# DSOXLAN_Schematic.net
KiCad netlist of a schematic drawn in Altium Designer
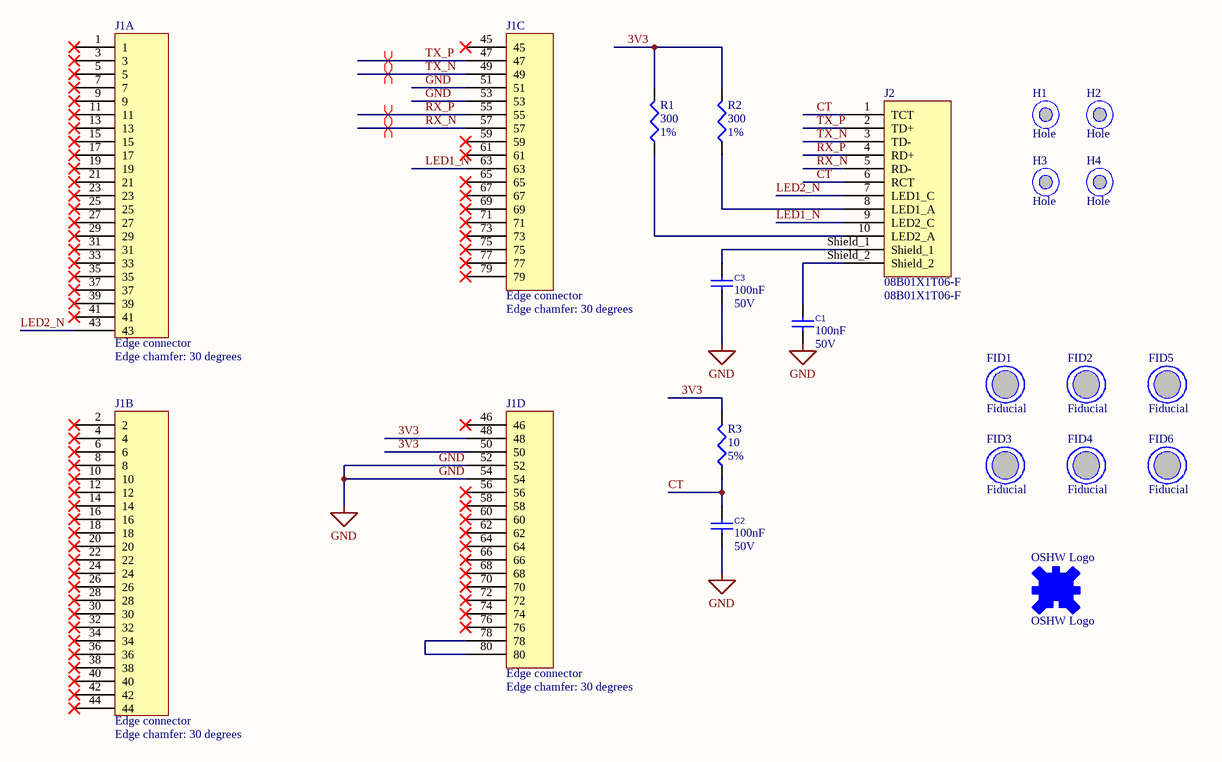
[diagram p0: DSOXLAN Schematic.SchDoc]

(export (version "E")
  (design (tool "Eeschema 10.0.6"))
  (components
    (comp (ref "C1")
      (value "100nF")
      (footprint "CAPC1005N")
      (description "Ceramic capcitor, X7R, 0402, 100nF, 10%, 50V")
      (fields
        (field (name "MANUFACTURER") "Yageo")
        (field (name "TOLERANCE") "10%")
        (field (name "VOLTAGE") "50V")
      )
      (libsource (lib "EnigmaTechComponents") (part "CAPC1005"))
    )
    (comp (ref "C2")
      (value "100nF")
      (footprint "CAPC1005N")
      (description "Ceramic capcitor, X7R, 0402, 100nF, 10%, 50V")
      (fields
        (field (name "MANUFACTURER") "Yageo")
        (field (name "TOLERANCE") "10%")
        (field (name "VOLTAGE") "50V")
      )
      (libsource (lib "EnigmaTechComponents") (part "CAPC1005"))
    )
    (comp (ref "C3")
      (value "100nF")
      (footprint "CAPC1005N")
      (description "Ceramic capcitor, X7R, 0402, 100nF, 10%, 50V")
      (fields
        (field (name "MANUFACTURER") "Yageo")
        (field (name "TOLERANCE") "10%")
        (field (name "VOLTAGE") "50V")
      )
      (libsource (lib "EnigmaTechComponents") (part "CAPC1005"))
    )
    (comp (ref "FID1")
      (value "Fiducial")
      (footprint "Fiducial 1mm")
      (description "Fiducial mark 1mm")
      (libsource (lib "EnigmaTechSCHLib") (part "Fiducial mark"))
    )
    (comp (ref "FID2")
      (value "Fiducial")
      (footprint "Fiducial 1mm")
      (description "Fiducial mark 1mm")
      (libsource (lib "EnigmaTechSCHLib") (part "Fiducial mark"))
    )
    (comp (ref "FID3")
      (value "Fiducial")
      (footprint "Fiducial 1mm")
      (description "Fiducial mark 1mm")
      (libsource (lib "EnigmaTechSCHLib") (part "Fiducial mark"))
    )
    (comp (ref "FID4")
      (value "Fiducial")
      (footprint "Fiducial 1mm")
      (description "Fiducial mark 1mm")
      (libsource (lib "EnigmaTechSCHLib") (part "Fiducial mark"))
    )
    (comp (ref "FID5")
      (value "Fiducial")
      (footprint "Fiducial 1mm")
      (description "Fiducial mark 1mm")
      (libsource (lib "EnigmaTechSCHLib") (part "Fiducial mark"))
    )
    (comp (ref "FID6")
      (value "Fiducial")
      (footprint "Fiducial 1mm")
      (description "Fiducial mark 1mm")
      (libsource (lib "EnigmaTechSCHLib") (part "Fiducial mark"))
    )
    (comp (ref "H1")
      (value "Hole")
      (footprint "Hole 3.2 non plated")
      (description "Non Plated Hole, 3.2mm ID")
      (libsource (lib "EnigmaTechSCHLib") (part "Hole 3.2mm NP"))
    )
    (comp (ref "H2")
      (value "Hole")
      (footprint "Hole 3.2 non plated")
      (description "Non Plated Hole, 3.2mm ID")
      (libsource (lib "EnigmaTechSCHLib") (part "Hole 3.2mm NP"))
    )
    (comp (ref "H3")
      (value "Hole")
      (footprint "Hole 3.2 non plated")
      (description "Non Plated Hole, 3.2mm ID")
      (libsource (lib "EnigmaTechSCHLib") (part "Hole 3.2mm NP"))
    )
    (comp (ref "H4")
      (value "Hole")
      (footprint "Hole 3.2 non plated")
      (description "Non Plated Hole, 3.2mm ID")
      (libsource (lib "EnigmaTechSCHLib") (part "Hole 3.2mm NP"))
    )
    (comp (ref "J1")
      (value "Edge connector")
      (footprint "Edge Connector 0.8mm 80P")
      (description "Edge contact 80pos 0.8p")
      (fields (field (name "EDGE CHAMFER") "30 degrees"))
      (libsource (lib "EnigmaTechConnectors") (part "Edge Connector 0.8mm 80 Pos"))
    )
    (comp (ref "J2")
      (value "08B01X1T06-F")
      (footprint "RJ45 BEL 08B0-1X1T-06-F")
      (description "RJ45 TH With magnetics")
      (fields
        (field (name "MANUFACTURER") "Bel Fuse")
        (field (name "MANUFACTURER PART NUMBER") "08B01X1T06-F")
      )
      (libsource (lib "EnigmaTechConnectors") (part "RJ45 T.H. W/Mag Bel Fuse"))
    )
    (comp (ref "OSHW Logo")
      (value "OSHW Logo")
      (footprint "OSHW Logo")
      (description "Solder mask logo")
      (libsource (lib "EnigmaTechSCHLib") (part "OSHW Logo"))
    )
    (comp (ref "R1")
      (value "300")
      (footprint "RESC1005N")
      (description "300Ohm 0402 1% resistor")
      (fields
        (field (name "MANUFACTURER") "Yageo")
        (field (name "PART NUMBER") "RA-300R-S00")
        (field (name "TOLERANCE") "1%")
      )
      (libsource (lib "EnigmaTechComponents") (part "RESC1005"))
    )
    (comp (ref "R2")
      (value "300")
      (footprint "RESC1005N")
      (description "300Ohm 0402 1% resistor")
      (fields
        (field (name "MANUFACTURER") "Yageo")
        (field (name "PART NUMBER") "RA-300R-S00")
        (field (name "TOLERANCE") "1%")
      )
      (libsource (lib "EnigmaTechComponents") (part "RESC1005"))
    )
    (comp (ref "R3")
      (value "10")
      (footprint "RESC1005N")
      (description "10 Ohm 0402 Resistor")
      (fields
        (field (name "MANUFACTURER") "Yageo")
        (field (name "PART NUMBER") "RA-10R0-S00")
        (field (name "TOLERANCE") "5%")
      )
      (libsource (lib "EnigmaTechComponents") (part "RESC1005"))
    )
  )
  (nets
    (net (code "1") (name "/3V3") (class "Default")
      (node (ref "J1") (pin "48") (pinfunction "48_48") (pintype "passive"))
      (node (ref "J1") (pin "50") (pinfunction "50_50") (pintype "passive"))
      (node (ref "R1") (pin "2") (pinfunction "2_2") (pintype "passive"))
      (node (ref "R2") (pin "2") (pinfunction "2_2") (pintype "passive"))
      (node (ref "R3") (pin "2") (pinfunction "2_2") (pintype "passive"))
    )
    (net (code "2") (name "/CT") (class "Default")
      (node (ref "C2") (pin "2") (pinfunction "2_2") (pintype "passive"))
      (node (ref "J2") (pin "1") (pinfunction "TCT_1") (pintype "passive"))
      (node (ref "J2") (pin "6") (pinfunction "RCT_6") (pintype "passive"))
      (node (ref "R3") (pin "1") (pinfunction "1_1") (pintype "passive"))
    )
    (net (code "3") (name "/LED1_N") (class "Default")
      (node (ref "J1") (pin "63") (pinfunction "63_63") (pintype "passive"))
      (node (ref "J2") (pin "9") (pinfunction "LED2_C_9") (pintype "passive"))
    )
    (net (code "4") (name "/LED2_N") (class "Default")
      (node (ref "J1") (pin "43") (pinfunction "43_43") (pintype "passive"))
      (node (ref "J2") (pin "7") (pinfunction "LED1_C_7") (pintype "passive"))
    )
    (net (code "5") (name "/RX_N") (class "Default")
      (node (ref "J1") (pin "57") (pinfunction "57_57") (pintype "passive"))
      (node (ref "J2") (pin "5") (pinfunction "RD-_5") (pintype "passive"))
    )
    (net (code "6") (name "/RX_P") (class "Default")
      (node (ref "J1") (pin "55") (pinfunction "55_55") (pintype "passive"))
      (node (ref "J2") (pin "4") (pinfunction "RD+_4") (pintype "passive"))
    )
    (net (code "7") (name "/TX_N") (class "Default")
      (node (ref "J1") (pin "49") (pinfunction "49_49") (pintype "passive"))
      (node (ref "J2") (pin "3") (pinfunction "TD-_3") (pintype "passive"))
    )
    (net (code "8") (name "/TX_P") (class "Default")
      (node (ref "J1") (pin "47") (pinfunction "47_47") (pintype "passive"))
      (node (ref "J2") (pin "2") (pinfunction "TD+_2") (pintype "passive"))
    )
    (net (code "9") (name "GND") (class "Default")
      (node (ref "C1") (pin "1") (pinfunction "1_1") (pintype "passive"))
      (node (ref "C2") (pin "1") (pinfunction "1_1") (pintype "passive"))
      (node (ref "C3") (pin "1") (pinfunction "1_1") (pintype "passive"))
      (node (ref "J1") (pin "51") (pinfunction "51_51") (pintype "passive"))
      (node (ref "J1") (pin "52") (pinfunction "52_52") (pintype "passive"))
      (node (ref "J1") (pin "53") (pinfunction "53_53") (pintype "passive"))
      (node (ref "J1") (pin "54") (pinfunction "54_54") (pintype "passive"))
    )
    (net (code "10") (name "Net-(C1-Pad2)") (class "Default")
      (node (ref "C1") (pin "2") (pinfunction "2_2") (pintype "passive"))
      (node (ref "J2") (pin "Shield_2") (pinfunction "Shield_2_Shield_2") (pintype "passive"))
    )
    (net (code "11") (name "Net-(C3-Pad2)") (class "Default")
      (node (ref "C3") (pin "2") (pinfunction "2_2") (pintype "passive"))
      (node (ref "J2") (pin "Shield_1") (pinfunction "Shield_1_Shield_1") (pintype "passive"))
    )
    (net (code "12") (name "Net-(J1-Pad78)") (class "Default")
      (node (ref "J1") (pin "78") (pinfunction "78_78") (pintype "passive"))
      (node (ref "J1") (pin "80") (pinfunction "80_80") (pintype "passive"))
    )
    (net (code "13") (name "Net-(J2-LED1_A)") (class "Default")
      (node (ref "J2") (pin "8") (pinfunction "LED1_A_8") (pintype "passive"))
      (node (ref "R2") (pin "1") (pinfunction "1_1") (pintype "passive"))
    )
    (net (code "14") (name "Net-(J2-LED2_A)") (class "Default")
      (node (ref "J2") (pin "10") (pinfunction "LED2_A_10") (pintype "passive"))
      (node (ref "R1") (pin "1") (pinfunction "1_1") (pintype "passive"))
    )
    (net (code "15") (name "unconnected-(J1-Pad1)") (class "Default")
      (node (ref "J1") (pin "1") (pinfunction "1_1") (pintype "passive+no_connect"))
    )
    (net (code "16") (name "unconnected-(J1-Pad2)") (class "Default")
      (node (ref "J1") (pin "2") (pinfunction "2_2") (pintype "passive+no_connect"))
    )
    (net (code "17") (name "unconnected-(J1-Pad3)") (class "Default")
      (node (ref "J1") (pin "3") (pinfunction "3_3") (pintype "passive+no_connect"))
    )
    (net (code "18") (name "unconnected-(J1-Pad4)") (class "Default")
      (node (ref "J1") (pin "4") (pinfunction "4_4") (pintype "passive+no_connect"))
    )
    (net (code "19") (name "unconnected-(J1-Pad5)") (class "Default")
      (node (ref "J1") (pin "5") (pinfunction "5_5") (pintype "passive+no_connect"))
    )
    (net (code "20") (name "unconnected-(J1-Pad6)") (class "Default")
      (node (ref "J1") (pin "6") (pinfunction "6_6") (pintype "passive+no_connect"))
    )
    (net (code "21") (name "unconnected-(J1-Pad7)") (class "Default")
      (node (ref "J1") (pin "7") (pinfunction "7_7") (pintype "passive+no_connect"))
    )
    (net (code "22") (name "unconnected-(J1-Pad8)") (class "Default")
      (node (ref "J1") (pin "8") (pinfunction "8_8") (pintype "passive+no_connect"))
    )
    (net (code "23") (name "unconnected-(J1-Pad9)") (class "Default")
      (node (ref "J1") (pin "9") (pinfunction "9_9") (pintype "passive+no_connect"))
    )
    (net (code "24") (name "unconnected-(J1-Pad10)") (class "Default")
      (node (ref "J1") (pin "10") (pinfunction "10_10") (pintype "passive+no_connect"))
    )
    (net (code "25") (name "unconnected-(J1-Pad11)") (class "Default")
      (node (ref "J1") (pin "11") (pinfunction "11_11") (pintype "passive+no_connect"))
    )
    (net (code "26") (name "unconnected-(J1-Pad12)") (class "Default")
      (node (ref "J1") (pin "12") (pinfunction "12_12") (pintype "passive+no_connect"))
    )
    (net (code "27") (name "unconnected-(J1-Pad13)") (class "Default")
      (node (ref "J1") (pin "13") (pinfunction "13_13") (pintype "passive+no_connect"))
    )
    (net (code "28") (name "unconnected-(J1-Pad14)") (class "Default")
      (node (ref "J1") (pin "14") (pinfunction "14_14") (pintype "passive+no_connect"))
    )
    (net (code "29") (name "unconnected-(J1-Pad15)") (class "Default")
      (node (ref "J1") (pin "15") (pinfunction "15_15") (pintype "passive+no_connect"))
    )
    (net (code "30") (name "unconnected-(J1-Pad16)") (class "Default")
      (node (ref "J1") (pin "16") (pinfunction "16_16") (pintype "passive+no_connect"))
    )
    (net (code "31") (name "unconnected-(J1-Pad17)") (class "Default")
      (node (ref "J1") (pin "17") (pinfunction "17_17") (pintype "passive+no_connect"))
    )
    (net (code "32") (name "unconnected-(J1-Pad18)") (class "Default")
      (node (ref "J1") (pin "18") (pinfunction "18_18") (pintype "passive+no_connect"))
    )
    (net (code "33") (name "unconnected-(J1-Pad19)") (class "Default")
      (node (ref "J1") (pin "19") (pinfunction "19_19") (pintype "passive+no_connect"))
    )
    (net (code "34") (name "unconnected-(J1-Pad20)") (class "Default")
      (node (ref "J1") (pin "20") (pinfunction "20_20") (pintype "passive+no_connect"))
    )
    (net (code "35") (name "unconnected-(J1-Pad21)") (class "Default")
      (node (ref "J1") (pin "21") (pinfunction "21_21") (pintype "passive+no_connect"))
    )
    (net (code "36") (name "unconnected-(J1-Pad22)") (class "Default")
      (node (ref "J1") (pin "22") (pinfunction "22_22") (pintype "passive+no_connect"))
    )
    (net (code "37") (name "unconnected-(J1-Pad23)") (class "Default")
      (node (ref "J1") (pin "23") (pinfunction "23_23") (pintype "passive+no_connect"))
    )
    (net (code "38") (name "unconnected-(J1-Pad24)") (class "Default")
      (node (ref "J1") (pin "24") (pinfunction "24_24") (pintype "passive+no_connect"))
    )
    (net (code "39") (name "unconnected-(J1-Pad25)") (class "Default")
      (node (ref "J1") (pin "25") (pinfunction "25_25") (pintype "passive+no_connect"))
    )
    (net (code "40") (name "unconnected-(J1-Pad26)") (class "Default")
      (node (ref "J1") (pin "26") (pinfunction "26_26") (pintype "passive+no_connect"))
    )
    (net (code "41") (name "unconnected-(J1-Pad27)") (class "Default")
      (node (ref "J1") (pin "27") (pinfunction "27_27") (pintype "passive+no_connect"))
    )
    (net (code "42") (name "unconnected-(J1-Pad28)") (class "Default")
      (node (ref "J1") (pin "28") (pinfunction "28_28") (pintype "passive+no_connect"))
    )
    (net (code "43") (name "unconnected-(J1-Pad29)") (class "Default")
      (node (ref "J1") (pin "29") (pinfunction "29_29") (pintype "passive+no_connect"))
    )
    (net (code "44") (name "unconnected-(J1-Pad30)") (class "Default")
      (node (ref "J1") (pin "30") (pinfunction "30_30") (pintype "passive+no_connect"))
    )
    (net (code "45") (name "unconnected-(J1-Pad31)") (class "Default")
      (node (ref "J1") (pin "31") (pinfunction "31_31") (pintype "passive+no_connect"))
    )
    (net (code "46") (name "unconnected-(J1-Pad32)") (class "Default")
      (node (ref "J1") (pin "32") (pinfunction "32_32") (pintype "passive+no_connect"))
    )
    (net (code "47") (name "unconnected-(J1-Pad33)") (class "Default")
      (node (ref "J1") (pin "33") (pinfunction "33_33") (pintype "passive+no_connect"))
    )
    (net (code "48") (name "unconnected-(J1-Pad34)") (class "Default")
      (node (ref "J1") (pin "34") (pinfunction "34_34") (pintype "passive+no_connect"))
    )
    (net (code "49") (name "unconnected-(J1-Pad35)") (class "Default")
      (node (ref "J1") (pin "35") (pinfunction "35_35") (pintype "passive+no_connect"))
    )
    (net (code "50") (name "unconnected-(J1-Pad36)") (class "Default")
      (node (ref "J1") (pin "36") (pinfunction "36_36") (pintype "passive+no_connect"))
    )
    (net (code "51") (name "unconnected-(J1-Pad37)") (class "Default")
      (node (ref "J1") (pin "37") (pinfunction "37_37") (pintype "passive+no_connect"))
    )
    (net (code "52") (name "unconnected-(J1-Pad38)") (class "Default")
      (node (ref "J1") (pin "38") (pinfunction "38_38") (pintype "passive+no_connect"))
    )
    (net (code "53") (name "unconnected-(J1-Pad39)") (class "Default")
      (node (ref "J1") (pin "39") (pinfunction "39_39") (pintype "passive+no_connect"))
    )
    (net (code "54") (name "unconnected-(J1-Pad40)") (class "Default")
      (node (ref "J1") (pin "40") (pinfunction "40_40") (pintype "passive+no_connect"))
    )
    (net (code "55") (name "unconnected-(J1-Pad41)") (class "Default")
      (node (ref "J1") (pin "41") (pinfunction "41_41") (pintype "passive+no_connect"))
    )
    (net (code "56") (name "unconnected-(J1-Pad42)") (class "Default")
      (node (ref "J1") (pin "42") (pinfunction "42_42") (pintype "passive+no_connect"))
    )
    (net (code "57") (name "unconnected-(J1-Pad44)") (class "Default")
      (node (ref "J1") (pin "44") (pinfunction "44_44") (pintype "passive+no_connect"))
    )
    (net (code "58") (name "unconnected-(J1-Pad45)") (class "Default")
      (node (ref "J1") (pin "45") (pinfunction "45_45") (pintype "passive+no_connect"))
    )
    (net (code "59") (name "unconnected-(J1-Pad46)") (class "Default")
      (node (ref "J1") (pin "46") (pinfunction "46_46") (pintype "passive+no_connect"))
    )
    (net (code "60") (name "unconnected-(J1-Pad56)") (class "Default")
      (node (ref "J1") (pin "56") (pinfunction "56_56") (pintype "passive+no_connect"))
    )
    (net (code "61") (name "unconnected-(J1-Pad58)") (class "Default")
      (node (ref "J1") (pin "58") (pinfunction "58_58") (pintype "passive+no_connect"))
    )
    (net (code "62") (name "unconnected-(J1-Pad59)") (class "Default")
      (node (ref "J1") (pin "59") (pinfunction "59_59") (pintype "passive+no_connect"))
    )
    (net (code "63") (name "unconnected-(J1-Pad60)") (class "Default")
      (node (ref "J1") (pin "60") (pinfunction "60_60") (pintype "passive+no_connect"))
    )
    (net (code "64") (name "unconnected-(J1-Pad61)") (class "Default")
      (node (ref "J1") (pin "61") (pinfunction "61_61") (pintype "passive+no_connect"))
    )
    (net (code "65") (name "unconnected-(J1-Pad62)") (class "Default")
      (node (ref "J1") (pin "62") (pinfunction "62_62") (pintype "passive+no_connect"))
    )
    (net (code "66") (name "unconnected-(J1-Pad64)") (class "Default")
      (node (ref "J1") (pin "64") (pinfunction "64_64") (pintype "passive+no_connect"))
    )
    (net (code "67") (name "unconnected-(J1-Pad65)") (class "Default")
      (node (ref "J1") (pin "65") (pinfunction "65_65") (pintype "passive+no_connect"))
    )
    (net (code "68") (name "unconnected-(J1-Pad66)") (class "Default")
      (node (ref "J1") (pin "66") (pinfunction "66_66") (pintype "passive+no_connect"))
    )
    (net (code "69") (name "unconnected-(J1-Pad67)") (class "Default")
      (node (ref "J1") (pin "67") (pinfunction "67_67") (pintype "passive+no_connect"))
    )
    (net (code "70") (name "unconnected-(J1-Pad68)") (class "Default")
      (node (ref "J1") (pin "68") (pinfunction "68_68") (pintype "passive+no_connect"))
    )
    (net (code "71") (name "unconnected-(J1-Pad69)") (class "Default")
      (node (ref "J1") (pin "69") (pinfunction "69_69") (pintype "passive+no_connect"))
    )
    (net (code "72") (name "unconnected-(J1-Pad70)") (class "Default")
      (node (ref "J1") (pin "70") (pinfunction "70_70") (pintype "passive+no_connect"))
    )
    (net (code "73") (name "unconnected-(J1-Pad71)") (class "Default")
      (node (ref "J1") (pin "71") (pinfunction "71_71") (pintype "passive+no_connect"))
    )
    (net (code "74") (name "unconnected-(J1-Pad72)") (class "Default")
      (node (ref "J1") (pin "72") (pinfunction "72_72") (pintype "passive+no_connect"))
    )
    (net (code "75") (name "unconnected-(J1-Pad73)") (class "Default")
      (node (ref "J1") (pin "73") (pinfunction "73_73") (pintype "passive+no_connect"))
    )
    (net (code "76") (name "unconnected-(J1-Pad74)") (class "Default")
      (node (ref "J1") (pin "74") (pinfunction "74_74") (pintype "passive+no_connect"))
    )
    (net (code "77") (name "unconnected-(J1-Pad75)") (class "Default")
      (node (ref "J1") (pin "75") (pinfunction "75_75") (pintype "passive+no_connect"))
    )
    (net (code "78") (name "unconnected-(J1-Pad76)") (class "Default")
      (node (ref "J1") (pin "76") (pinfunction "76_76") (pintype "passive+no_connect"))
    )
    (net (code "79") (name "unconnected-(J1-Pad77)") (class "Default")
      (node (ref "J1") (pin "77") (pinfunction "77_77") (pintype "passive+no_connect"))
    )
    (net (code "80") (name "unconnected-(J1-Pad79)") (class "Default")
      (node (ref "J1") (pin "79") (pinfunction "79_79") (pintype "passive+no_connect"))
    )
  )
)
